# MezzanineDCDC_8045.net
KiCad netlist of a schematic drawn in Altium Designer
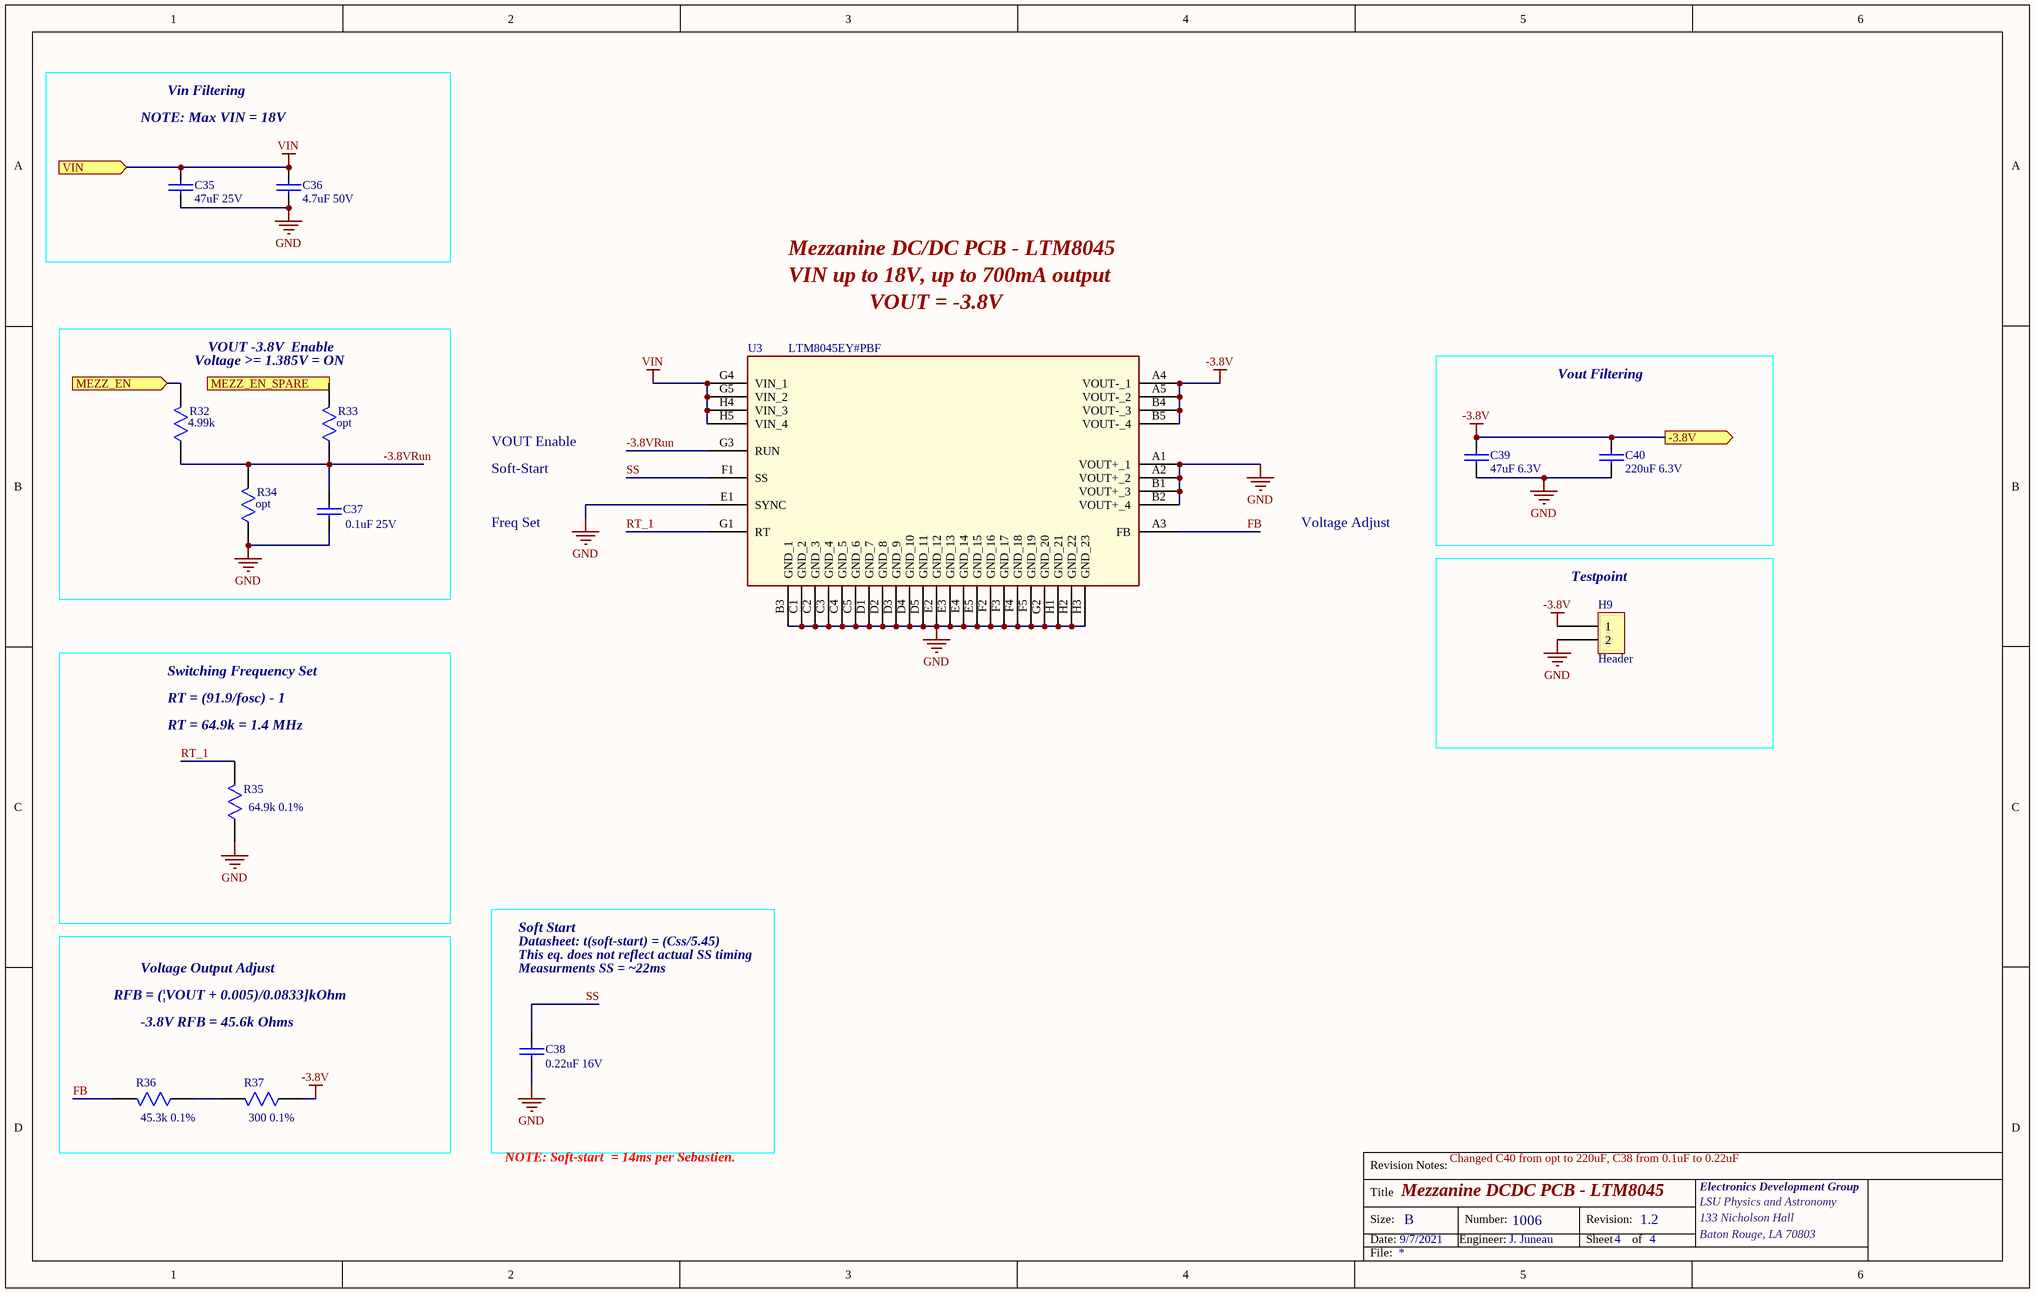
[diagram p0: MezzanineDCDC_8045.SchDoc]

(export (version "E")
  (design (tool "Eeschema 10.0.6"))
  (components
    (comp (ref "C35")
      (value "47uF 25V")
      (footprint "CAP 1206 TDK")
      (description "47µF ±20% 25V Ceramic Capacitor X5R 1206 (3216 Metric)")
      (fields (field (name "Comment") "C3216X5R1E476M160AC"))
      (libsource (lib "MezzanineDCDC") (part "Capacitor 1206"))
    )
    (comp (ref "C36")
      (value "4.7uF 50V")
      (footprint "CAP 1206 TDK")
      (description "4.7µF ±10% 50V Ceramic Capacitor X5R 1206 (3216 Metric)")
      (fields (field (name "Comment") "UMK316BJ475KL-T"))
      (libsource (lib "MezzanineDCDC") (part "Capacitor 1206"))
    )
    (comp (ref "C37")
      (value "0.1uF 25V")
      (footprint "Cap 0603 TDK")
      (description "CAP CER 0.1UF 25V X7R 0603")
      (fields (field (name "Comment") "C1608X7R1E104K080AA"))
      (libsource (lib "MezzanineDCDC") (part "Capacitor 0603 TDK"))
    )
    (comp (ref "C38")
      (value "0.22uF 16V")
      (footprint "Cap 0603 TDK")
      (description "0.22 µF ±10% 16V Ceramic Capacitor X5R 0603 (1608 Metric)")
      (fields (field (name "Comment") "0603YD224KAT2A"))
      (libsource (lib "MezzanineDCDC") (part "Capacitor 0603 TDK"))
    )
    (comp (ref "C39")
      (value "47uF 6.3V")
      (footprint "CAP 1206 TDK 2.3 Height")
      (description "47µF ±20% 6.3V Ceramic Capacitor X5R 1206 (3216 Metric)")
      (fields (field (name "Comment") "12066D476MAT4A"))
      (libsource (lib "MezzanineDCDC") (part "Capacitor 1206 2.3mmHeight"))
    )
    (comp (ref "C40")
      (value "220uF 6.3V")
      (footprint "CAP 1206 TDK 2.3 Height")
      (description "220 µF ±20% 6.3V Ceramic Capacitor X5R 1206 (3216 Metric)")
      (fields (field (name "Comment") "GRM31CR60J227ME11L"))
      (libsource (lib "MezzanineDCDC") (part "Capacitor 1206 2.3mmHeight"))
    )
    (comp (ref "H9")
      (value "Header")
      (footprint "Header 2Pin")
      (description "Connector Header Through Hole 2 position 0.100\" (2.54mm)")
      (libsource (lib "MezzanineDCDC") (part "Header - 2Pin"))
    )
    (comp (ref "R32")
      (value "4.99k")
      (footprint "Resistor ERJ2G/CRCW 0402")
      (description "RES, Thick Film, 4.99 kOhm, 1.0 %, 1/16 W, SMD, 0402")
      (fields (field (name "Comment") "CRCW04024K99FKED"))
      (libsource (lib "MezzanineDCDC") (part "ERJ2G Resistor 0402"))
    )
    (comp (ref "R33")
      (value "opt")
      (footprint "Resistor ERJ2G/CRCW 0402")
      (description "Resistor 0402")
      (libsource (lib "MezzanineDCDC") (part "ERJ2G Resistor 0402"))
    )
    (comp (ref "R34")
      (value "opt")
      (footprint "Resistor ERJ2G/CRCW 0402")
      (description "Resistor 0402")
      (libsource (lib "MezzanineDCDC") (part "ERJ2G Resistor 0402"))
    )
    (comp (ref "R35")
      (value "64.9k 0.1%")
      (footprint "Resistor 0603 - ERJ")
      (fields (field (name "Comment") "ERJ-PB3B6492V"))
      (libsource (lib "MezzanineDCDC") (part "Resistor 0603"))
    )
    (comp (ref "R36")
      (value "45.3k 0.1%")
      (footprint "Resistor 0603 - ERJ")
      (description "RES SMD 45.3KOHM 0.1% 1/10W 0603")
      (fields (field (name "Comment") "ERA-3AEB4532V"))
      (libsource (lib "MezzanineDCDC") (part "Resistor 0603"))
    )
    (comp (ref "R37")
      (value "300 0.1%")
      (footprint "Resistor 0603 - ERJ")
      (description "RES SMD 300 OHM 0.1% 1/10W 0603")
      (fields (field (name "Comment") "ERA-3AEB301V"))
      (libsource (lib "MezzanineDCDC") (part "Resistor 0603"))
    )
    (comp (ref "U3")
      (value "LTM8045EY#PBF")
      (footprint "LTM8045")
      (description "Non-Isolated PoL Module DC DC Converter Output -2.5 ~ -15V, 2.5 ~ 15V - - 700mA 2.8V - 18V Input")
      (libsource (lib "MezzanineDCDC") (part "LTM8045"))
    )
  )
  (nets
    (net (code "1") (name "-3.8V") (class "Default")
      (node (ref "C39") (pin "1") (pinfunction "1_1") (pintype "passive"))
      (node (ref "C40") (pin "1") (pinfunction "1_1") (pintype "passive"))
      (node (ref "H9") (pin "1") (pinfunction "1_1") (pintype "passive"))
      (node (ref "R37") (pin "1") (pinfunction "0_1") (pintype "passive"))
      (node (ref "U3") (pin "A4") (pinfunction "VOUT-_1_A4") (pintype "passive"))
      (node (ref "U3") (pin "A5") (pinfunction "VOUT-_2_A5") (pintype "passive"))
      (node (ref "U3") (pin "B4") (pinfunction "VOUT-_3_B4") (pintype "passive"))
      (node (ref "U3") (pin "B5") (pinfunction "VOUT-_4_B5") (pintype "passive"))
    )
    (net (code "2") (name "/-3.8VRun") (class "Default")
      (node (ref "C37") (pin "1") (pinfunction "1_1") (pintype "passive"))
      (node (ref "R32") (pin "1") (pinfunction "0_1") (pintype "passive"))
      (node (ref "R33") (pin "1") (pinfunction "0_1") (pintype "passive"))
      (node (ref "R34") (pin "2") (pinfunction "1_2") (pintype "passive"))
      (node (ref "U3") (pin "G3") (pinfunction "RUN_G3") (pintype "passive"))
    )
    (net (code "3") (name "/FB") (class "Default")
      (node (ref "R36") (pin "2") (pinfunction "1_2") (pintype "passive"))
      (node (ref "U3") (pin "A3") (pinfunction "FB_A3") (pintype "passive"))
    )
    (net (code "4") (name "/MEZZ_EN") (class "Default")
      (node (ref "R32") (pin "2") (pinfunction "1_2") (pintype "passive"))
    )
    (net (code "5") (name "/MEZZ_EN_SPARE") (class "Default")
      (node (ref "R33") (pin "2") (pinfunction "1_2") (pintype "passive"))
    )
    (net (code "6") (name "/RT_1") (class "Default")
      (node (ref "R35") (pin "2") (pinfunction "1_2") (pintype "passive"))
      (node (ref "U3") (pin "G1") (pinfunction "RT_G1") (pintype "passive"))
    )
    (net (code "7") (name "/SS") (class "Default")
      (node (ref "C38") (pin "1") (pinfunction "1_1") (pintype "passive"))
      (node (ref "U3") (pin "F1") (pinfunction "SS_F1") (pintype "passive"))
    )
    (net (code "8") (name "GND") (class "Default")
      (node (ref "C35") (pin "2") (pinfunction "2_2") (pintype "passive"))
      (node (ref "C36") (pin "2") (pinfunction "2_2") (pintype "passive"))
      (node (ref "C37") (pin "2") (pinfunction "2_2") (pintype "passive"))
      (node (ref "C38") (pin "2") (pinfunction "2_2") (pintype "passive"))
      (node (ref "C39") (pin "2") (pinfunction "2_2") (pintype "passive"))
      (node (ref "C40") (pin "2") (pinfunction "2_2") (pintype "passive"))
      (node (ref "H9") (pin "2") (pinfunction "2_2") (pintype "passive"))
      (node (ref "R34") (pin "1") (pinfunction "0_1") (pintype "passive"))
      (node (ref "R35") (pin "1") (pinfunction "0_1") (pintype "passive"))
      (node (ref "U3") (pin "A1") (pinfunction "VOUT+_1_A1") (pintype "passive"))
      (node (ref "U3") (pin "A2") (pinfunction "VOUT+_2_A2") (pintype "passive"))
      (node (ref "U3") (pin "B1") (pinfunction "VOUT+_3_B1") (pintype "passive"))
      (node (ref "U3") (pin "B2") (pinfunction "VOUT+_4_B2") (pintype "passive"))
      (node (ref "U3") (pin "B3") (pinfunction "GND_1_B3") (pintype "passive"))
      (node (ref "U3") (pin "C1") (pinfunction "GND_2_C1") (pintype "passive"))
      (node (ref "U3") (pin "C2") (pinfunction "GND_3_C2") (pintype "passive"))
      (node (ref "U3") (pin "C3") (pinfunction "GND_4_C3") (pintype "passive"))
      (node (ref "U3") (pin "C4") (pinfunction "GND_5_C4") (pintype "passive"))
      (node (ref "U3") (pin "C5") (pinfunction "GND_6_C5") (pintype "passive"))
      (node (ref "U3") (pin "D1") (pinfunction "GND_7_D1") (pintype "passive"))
      (node (ref "U3") (pin "D2") (pinfunction "GND_8_D2") (pintype "passive"))
      (node (ref "U3") (pin "D3") (pinfunction "GND_9_D3") (pintype "passive"))
      (node (ref "U3") (pin "D4") (pinfunction "GND_10_D4") (pintype "passive"))
      (node (ref "U3") (pin "D5") (pinfunction "GND_11_D5") (pintype "passive"))
      (node (ref "U3") (pin "E1") (pinfunction "SYNC_E1") (pintype "passive"))
      (node (ref "U3") (pin "E2") (pinfunction "GND_12_E2") (pintype "passive"))
      (node (ref "U3") (pin "E3") (pinfunction "GND_13_E3") (pintype "passive"))
      (node (ref "U3") (pin "E4") (pinfunction "GND_14_E4") (pintype "passive"))
      (node (ref "U3") (pin "E5") (pinfunction "GND_15_E5") (pintype "passive"))
      (node (ref "U3") (pin "F2") (pinfunction "GND_16_F2") (pintype "passive"))
      (node (ref "U3") (pin "F3") (pinfunction "GND_17_F3") (pintype "passive"))
      (node (ref "U3") (pin "F4") (pinfunction "GND_18_F4") (pintype "passive"))
      (node (ref "U3") (pin "F5") (pinfunction "GND_19_F5") (pintype "passive"))
      (node (ref "U3") (pin "G2") (pinfunction "GND_20_G2") (pintype "passive"))
      (node (ref "U3") (pin "H1") (pinfunction "GND_21_H1") (pintype "passive"))
      (node (ref "U3") (pin "H2") (pinfunction "GND_22_H2") (pintype "passive"))
      (node (ref "U3") (pin "H3") (pinfunction "GND_23_H3") (pintype "passive"))
    )
    (net (code "9") (name "Net-(R36-0)") (class "Default")
      (node (ref "R36") (pin "1") (pinfunction "0_1") (pintype "passive"))
      (node (ref "R37") (pin "2") (pinfunction "1_2") (pintype "passive"))
    )
    (net (code "10") (name "VIN") (class "Default")
      (node (ref "C35") (pin "1") (pinfunction "1_1") (pintype "passive"))
      (node (ref "C36") (pin "1") (pinfunction "1_1") (pintype "passive"))
      (node (ref "U3") (pin "G4") (pinfunction "VIN_1_G4") (pintype "passive"))
      (node (ref "U3") (pin "G5") (pinfunction "VIN_2_G5") (pintype "passive"))
      (node (ref "U3") (pin "H4") (pinfunction "VIN_3_H4") (pintype "passive"))
      (node (ref "U3") (pin "H5") (pinfunction "VIN_4_H5") (pintype "passive"))
    )
  )
)
